# main.net
KiCad netlist of a schematic drawn in Altium Designer
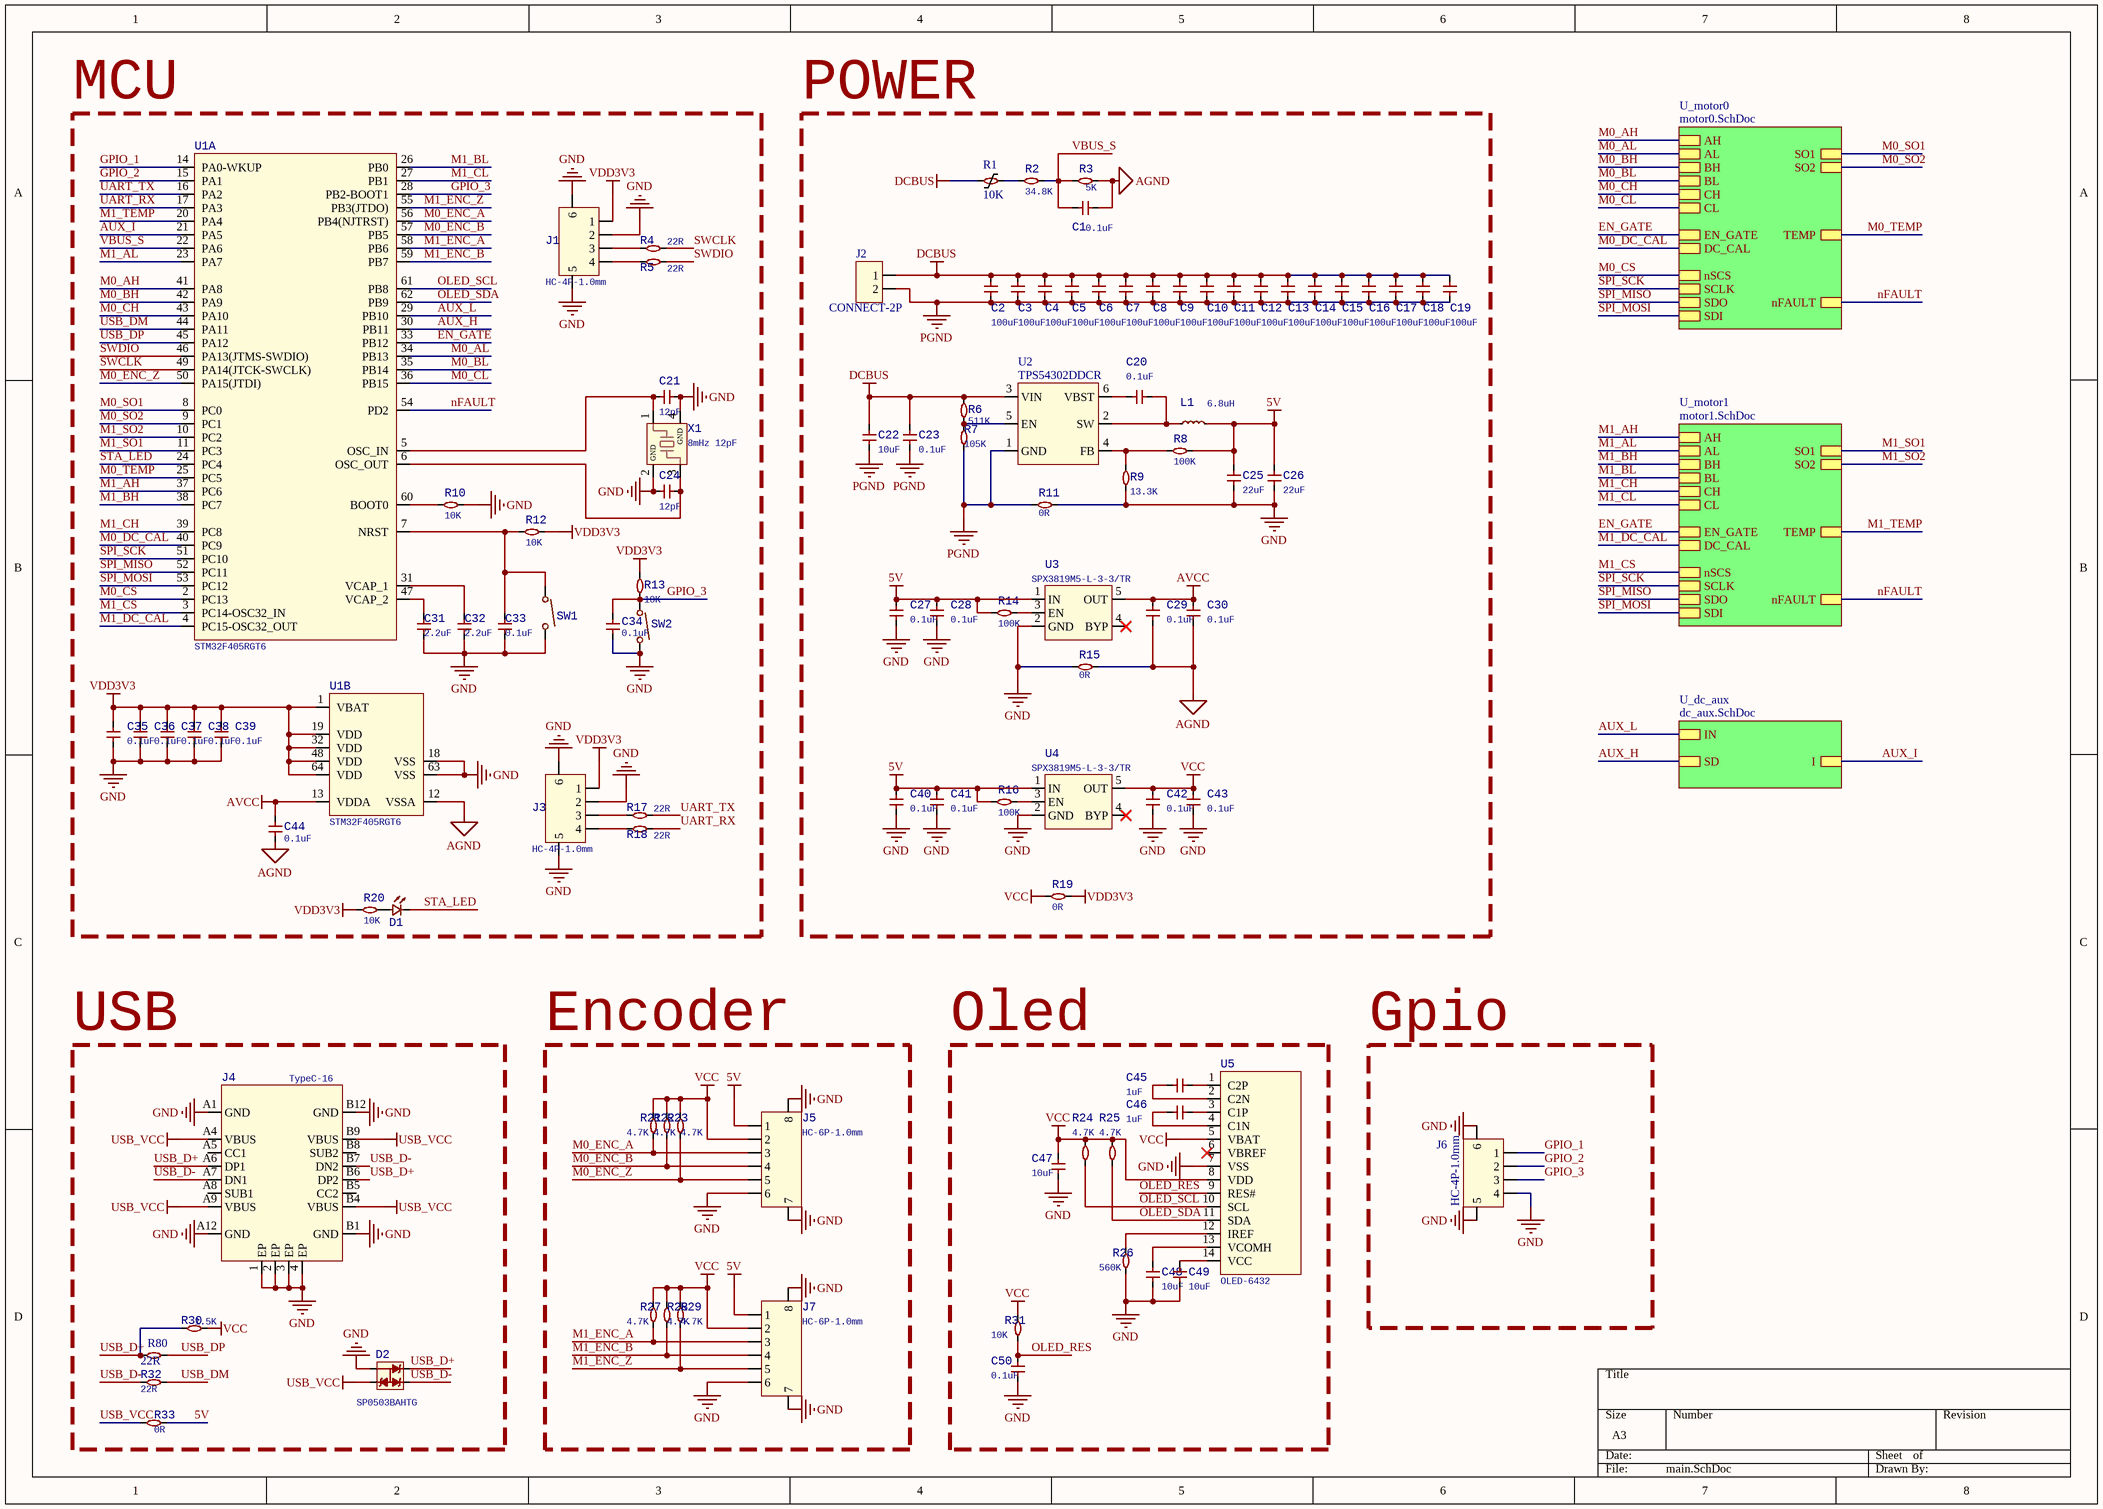
[diagram p0: main.SchDoc]

(export (version "E")
  (design (tool "Eeschema 10.0.6"))
  (components
    (comp (ref "C1")
      (value "0.1uF")
      (footprint "C0402")
      (description "贴片电容")
      (fields
        (field (name "MANUFACTURER") "SAMSUNG(三星)")
        (field (name "MANUFACTURER PART") "CL05A105KP5NNND")
      )
      (libsource (lib "schLibrary") (part "CAP"))
    )
    (comp (ref "C2")
      (value "100uF")
      (footprint "C1206")
      (description "贴片电容")
      (fields
        (field (name "MANUFACTURER") "SAMSUNG(三星)")
        (field (name "MANUFACTURER PART") "CL05A105KP5NNND")
      )
      (libsource (lib "schLibrary") (part "CAP"))
    )
    (comp (ref "C3")
      (value "100uF")
      (footprint "C1206")
      (description "贴片电容")
      (fields
        (field (name "MANUFACTURER") "SAMSUNG(三星)")
        (field (name "MANUFACTURER PART") "CL05A105KP5NNND")
      )
      (libsource (lib "schLibrary") (part "CAP"))
    )
    (comp (ref "C4")
      (value "100uF")
      (footprint "C1206")
      (description "贴片电容")
      (fields
        (field (name "MANUFACTURER") "SAMSUNG(三星)")
        (field (name "MANUFACTURER PART") "CL05A105KP5NNND")
      )
      (libsource (lib "schLibrary") (part "CAP"))
    )
    (comp (ref "C5")
      (value "100uF")
      (footprint "C1206")
      (description "贴片电容")
      (fields
        (field (name "MANUFACTURER") "SAMSUNG(三星)")
        (field (name "MANUFACTURER PART") "CL05A105KP5NNND")
      )
      (libsource (lib "schLibrary") (part "CAP"))
    )
    (comp (ref "C6")
      (value "100uF")
      (footprint "C1206")
      (description "贴片电容")
      (fields
        (field (name "MANUFACTURER") "SAMSUNG(三星)")
        (field (name "MANUFACTURER PART") "CL05A105KP5NNND")
      )
      (libsource (lib "schLibrary") (part "CAP"))
    )
    (comp (ref "C7")
      (value "100uF")
      (footprint "C1206")
      (description "贴片电容")
      (fields
        (field (name "MANUFACTURER") "SAMSUNG(三星)")
        (field (name "MANUFACTURER PART") "CL05A105KP5NNND")
      )
      (libsource (lib "schLibrary") (part "CAP"))
    )
    (comp (ref "C8")
      (value "100uF")
      (footprint "C1206")
      (description "贴片电容")
      (fields
        (field (name "MANUFACTURER") "SAMSUNG(三星)")
        (field (name "MANUFACTURER PART") "CL05A105KP5NNND")
      )
      (libsource (lib "schLibrary") (part "CAP"))
    )
    (comp (ref "C9")
      (value "100uF")
      (footprint "C1206")
      (description "贴片电容")
      (fields
        (field (name "MANUFACTURER") "SAMSUNG(三星)")
        (field (name "MANUFACTURER PART") "CL05A105KP5NNND")
      )
      (libsource (lib "schLibrary") (part "CAP"))
    )
    (comp (ref "C10")
      (value "100uF")
      (footprint "C1206")
      (description "贴片电容")
      (fields
        (field (name "MANUFACTURER") "SAMSUNG(三星)")
        (field (name "MANUFACTURER PART") "CL05A105KP5NNND")
      )
      (libsource (lib "schLibrary") (part "CAP"))
    )
    (comp (ref "C11")
      (value "100uF")
      (footprint "C1206")
      (description "贴片电容")
      (fields
        (field (name "MANUFACTURER") "SAMSUNG(三星)")
        (field (name "MANUFACTURER PART") "CL05A105KP5NNND")
      )
      (libsource (lib "schLibrary") (part "CAP"))
    )
    (comp (ref "C12")
      (value "100uF")
      (footprint "C1206")
      (description "贴片电容")
      (fields
        (field (name "MANUFACTURER") "SAMSUNG(三星)")
        (field (name "MANUFACTURER PART") "CL05A105KP5NNND")
      )
      (libsource (lib "schLibrary") (part "CAP"))
    )
    (comp (ref "C13")
      (value "100uF")
      (footprint "C1206")
      (description "贴片电容")
      (fields
        (field (name "MANUFACTURER") "SAMSUNG(三星)")
        (field (name "MANUFACTURER PART") "CL05A105KP5NNND")
      )
      (libsource (lib "schLibrary") (part "CAP"))
    )
    (comp (ref "C14")
      (value "100uF")
      (footprint "C1206")
      (description "贴片电容")
      (fields
        (field (name "MANUFACTURER") "SAMSUNG(三星)")
        (field (name "MANUFACTURER PART") "CL05A105KP5NNND")
      )
      (libsource (lib "schLibrary") (part "CAP"))
    )
    (comp (ref "C15")
      (value "100uF")
      (footprint "C1206")
      (description "贴片电容")
      (fields
        (field (name "MANUFACTURER") "SAMSUNG(三星)")
        (field (name "MANUFACTURER PART") "CL05A105KP5NNND")
      )
      (libsource (lib "schLibrary") (part "CAP"))
    )
    (comp (ref "C16")
      (value "100uF")
      (footprint "C1206")
      (description "贴片电容")
      (fields
        (field (name "MANUFACTURER") "SAMSUNG(三星)")
        (field (name "MANUFACTURER PART") "CL05A105KP5NNND")
      )
      (libsource (lib "schLibrary") (part "CAP"))
    )
    (comp (ref "C17")
      (value "100uF")
      (footprint "C1206")
      (description "贴片电容")
      (fields
        (field (name "MANUFACTURER") "SAMSUNG(三星)")
        (field (name "MANUFACTURER PART") "CL05A105KP5NNND")
      )
      (libsource (lib "schLibrary") (part "CAP"))
    )
    (comp (ref "C18")
      (value "100uF")
      (footprint "C1206")
      (description "贴片电容")
      (fields
        (field (name "MANUFACTURER") "SAMSUNG(三星)")
        (field (name "MANUFACTURER PART") "CL05A105KP5NNND")
      )
      (libsource (lib "schLibrary") (part "CAP"))
    )
    (comp (ref "C19")
      (value "100uF")
      (footprint "C1206")
      (description "贴片电容")
      (fields
        (field (name "MANUFACTURER") "SAMSUNG(三星)")
        (field (name "MANUFACTURER PART") "CL05A105KP5NNND")
      )
      (libsource (lib "schLibrary") (part "CAP"))
    )
    (comp (ref "C20")
      (value "0.1uF")
      (footprint "C0402")
      (description "贴片电容")
      (fields
        (field (name "MANUFACTURER") "SAMSUNG(三星)")
        (field (name "MANUFACTURER PART") "CL05A105KP5NNND")
      )
      (libsource (lib "schLibrary") (part "CAP"))
    )
    (comp (ref "C21")
      (value "12pF")
      (footprint "C0402")
      (description "贴片电容")
      (fields
        (field (name "MANUFACTURER") "SAMSUNG(三星)")
        (field (name "MANUFACTURER PART") "CL05A105KP5NNND")
      )
      (libsource (lib "schLibrary") (part "CAP"))
    )
    (comp (ref "C22")
      (value "10uF")
      (footprint "C0402")
      (description "贴片电容")
      (fields
        (field (name "MANUFACTURER") "SAMSUNG(三星)")
        (field (name "MANUFACTURER PART") "CL05A105KP5NNND")
      )
      (libsource (lib "schLibrary") (part "CAP"))
    )
    (comp (ref "C23")
      (value "0.1uF")
      (footprint "C0402")
      (description "贴片电容")
      (fields
        (field (name "MANUFACTURER") "SAMSUNG(三星)")
        (field (name "MANUFACTURER PART") "CL05A105KP5NNND")
      )
      (libsource (lib "schLibrary") (part "CAP"))
    )
    (comp (ref "C24")
      (value "12pF")
      (footprint "C0402")
      (description "贴片电容")
      (fields
        (field (name "MANUFACTURER") "SAMSUNG(三星)")
        (field (name "MANUFACTURER PART") "CL05A105KP5NNND")
      )
      (libsource (lib "schLibrary") (part "CAP"))
    )
    (comp (ref "C25")
      (value "22uF")
      (footprint "C0805")
      (description "贴片电容")
      (fields
        (field (name "MANUFACTURER") "SAMSUNG(三星)")
        (field (name "MANUFACTURER PART") "CL05A105KP5NNND")
      )
      (libsource (lib "schLibrary") (part "CAP"))
    )
    (comp (ref "C26")
      (value "22uF")
      (footprint "C0805")
      (description "贴片电容")
      (fields
        (field (name "MANUFACTURER") "SAMSUNG(三星)")
        (field (name "MANUFACTURER PART") "CL05A105KP5NNND")
      )
      (libsource (lib "schLibrary") (part "CAP"))
    )
    (comp (ref "C27")
      (value "0.1uF")
      (footprint "C0402")
      (description "贴片电容")
      (fields
        (field (name "MANUFACTURER") "SAMSUNG(三星)")
        (field (name "MANUFACTURER PART") "CL05A105KP5NNND")
      )
      (libsource (lib "schLibrary") (part "CAP"))
    )
    (comp (ref "C28")
      (value "0.1uF")
      (footprint "C0402")
      (description "贴片电容")
      (fields
        (field (name "MANUFACTURER") "SAMSUNG(三星)")
        (field (name "MANUFACTURER PART") "CL05A105KP5NNND")
      )
      (libsource (lib "schLibrary") (part "CAP"))
    )
    (comp (ref "C29")
      (value "0.1uF")
      (footprint "C0402")
      (description "贴片电容")
      (fields
        (field (name "MANUFACTURER") "SAMSUNG(三星)")
        (field (name "MANUFACTURER PART") "CL05A105KP5NNND")
      )
      (libsource (lib "schLibrary") (part "CAP"))
    )
    (comp (ref "C30")
      (value "0.1uF")
      (footprint "C0402")
      (description "贴片电容")
      (fields
        (field (name "MANUFACTURER") "SAMSUNG(三星)")
        (field (name "MANUFACTURER PART") "CL05A105KP5NNND")
      )
      (libsource (lib "schLibrary") (part "CAP"))
    )
    (comp (ref "C31")
      (value "2.2uF")
      (footprint "C0402")
      (description "贴片电容")
      (fields
        (field (name "MANUFACTURER") "SAMSUNG(三星)")
        (field (name "MANUFACTURER PART") "CL05A105KP5NNND")
      )
      (libsource (lib "schLibrary") (part "CAP"))
    )
    (comp (ref "C32")
      (value "2.2uF")
      (footprint "C0402")
      (description "贴片电容")
      (fields
        (field (name "MANUFACTURER") "SAMSUNG(三星)")
        (field (name "MANUFACTURER PART") "CL05A105KP5NNND")
      )
      (libsource (lib "schLibrary") (part "CAP"))
    )
    (comp (ref "C33")
      (value "0.1uF")
      (footprint "C0402")
      (description "贴片电容")
      (fields
        (field (name "MANUFACTURER") "SAMSUNG(三星)")
        (field (name "MANUFACTURER PART") "CL05A105KP5NNND")
      )
      (libsource (lib "schLibrary") (part "CAP"))
    )
    (comp (ref "C34")
      (value "0.1uF")
      (footprint "C0402")
      (description "贴片电容")
      (fields
        (field (name "MANUFACTURER") "SAMSUNG(三星)")
        (field (name "MANUFACTURER PART") "CL05A105KP5NNND")
      )
      (libsource (lib "schLibrary") (part "CAP"))
    )
    (comp (ref "C35")
      (value "0.1uF")
      (footprint "C0402")
      (description "贴片电容")
      (fields
        (field (name "MANUFACTURER") "SAMSUNG(三星)")
        (field (name "MANUFACTURER PART") "CL05A105KP5NNND")
      )
      (libsource (lib "schLibrary") (part "CAP"))
    )
    (comp (ref "C36")
      (value "0.1uF")
      (footprint "C0402")
      (description "贴片电容")
      (fields
        (field (name "MANUFACTURER") "SAMSUNG(三星)")
        (field (name "MANUFACTURER PART") "CL05A105KP5NNND")
      )
      (libsource (lib "schLibrary") (part "CAP"))
    )
    (comp (ref "C37")
      (value "0.1uF")
      (footprint "C0402")
      (description "贴片电容")
      (fields
        (field (name "MANUFACTURER") "SAMSUNG(三星)")
        (field (name "MANUFACTURER PART") "CL05A105KP5NNND")
      )
      (libsource (lib "schLibrary") (part "CAP"))
    )
    (comp (ref "C38")
      (value "0.1uF")
      (footprint "C0402")
      (description "贴片电容")
      (fields
        (field (name "MANUFACTURER") "SAMSUNG(三星)")
        (field (name "MANUFACTURER PART") "CL05A105KP5NNND")
      )
      (libsource (lib "schLibrary") (part "CAP"))
    )
    (comp (ref "C39")
      (value "0.1uF")
      (footprint "C0402")
      (description "贴片电容")
      (fields
        (field (name "MANUFACTURER") "SAMSUNG(三星)")
        (field (name "MANUFACTURER PART") "CL05A105KP5NNND")
      )
      (libsource (lib "schLibrary") (part "CAP"))
    )
    (comp (ref "C40")
      (value "0.1uF")
      (footprint "C0402")
      (description "贴片电容")
      (fields
        (field (name "MANUFACTURER") "SAMSUNG(三星)")
        (field (name "MANUFACTURER PART") "CL05A105KP5NNND")
      )
      (libsource (lib "schLibrary") (part "CAP"))
    )
    (comp (ref "C41")
      (value "0.1uF")
      (footprint "C0402")
      (description "贴片电容")
      (fields
        (field (name "MANUFACTURER") "SAMSUNG(三星)")
        (field (name "MANUFACTURER PART") "CL05A105KP5NNND")
      )
      (libsource (lib "schLibrary") (part "CAP"))
    )
    (comp (ref "C42")
      (value "0.1uF")
      (footprint "C0402")
      (description "贴片电容")
      (fields
        (field (name "MANUFACTURER") "SAMSUNG(三星)")
        (field (name "MANUFACTURER PART") "CL05A105KP5NNND")
      )
      (libsource (lib "schLibrary") (part "CAP"))
    )
    (comp (ref "C43")
      (value "0.1uF")
      (footprint "C0402")
      (description "贴片电容")
      (fields
        (field (name "MANUFACTURER") "SAMSUNG(三星)")
        (field (name "MANUFACTURER PART") "CL05A105KP5NNND")
      )
      (libsource (lib "schLibrary") (part "CAP"))
    )
    (comp (ref "C44")
      (value "0.1uF")
      (footprint "C0402")
      (description "贴片电容")
      (fields
        (field (name "MANUFACTURER") "SAMSUNG(三星)")
        (field (name "MANUFACTURER PART") "CL05A105KP5NNND")
      )
      (libsource (lib "schLibrary") (part "CAP"))
    )
    (comp (ref "C45")
      (value "1uF")
      (footprint "C0402")
      (description "贴片电容")
      (fields
        (field (name "MANUFACTURER") "SAMSUNG(三星)")
        (field (name "MANUFACTURER PART") "CL05A105KP5NNND")
      )
      (libsource (lib "schLibrary") (part "CAP"))
    )
    (comp (ref "C46")
      (value "1uF")
      (footprint "C0402")
      (description "贴片电容")
      (fields
        (field (name "MANUFACTURER") "SAMSUNG(三星)")
        (field (name "MANUFACTURER PART") "CL05A105KP5NNND")
      )
      (libsource (lib "schLibrary") (part "CAP"))
    )
    (comp (ref "C47")
      (value "10uF")
      (footprint "C0402")
      (description "贴片电容")
      (fields
        (field (name "MANUFACTURER") "SAMSUNG(三星)")
        (field (name "MANUFACTURER PART") "CL05A105KP5NNND")
      )
      (libsource (lib "schLibrary") (part "CAP"))
    )
    (comp (ref "C48")
      (value "10uF")
      (footprint "C0402")
      (description "贴片电容")
      (fields
        (field (name "MANUFACTURER") "SAMSUNG(三星)")
        (field (name "MANUFACTURER PART") "CL05A105KP5NNND")
      )
      (libsource (lib "schLibrary") (part "CAP"))
    )
    (comp (ref "C49")
      (value "10uF")
      (footprint "C0402")
      (description "贴片电容")
      (fields
        (field (name "MANUFACTURER") "SAMSUNG(三星)")
        (field (name "MANUFACTURER PART") "CL05A105KP5NNND")
      )
      (libsource (lib "schLibrary") (part "CAP"))
    )
    (comp (ref "C50")
      (value "0.1uF")
      (footprint "C0402")
      (description "贴片电容")
      (fields
        (field (name "MANUFACTURER") "SAMSUNG(三星)")
        (field (name "MANUFACTURER PART") "CL05A105KP5NNND")
      )
      (libsource (lib "schLibrary") (part "CAP"))
    )
    (comp (ref "D1")
      (value "LED")
      (footprint "LED-0402")
      (description "贴片发光二极管")
      (fields
        (field (name "MANUFACTURER") "SAMSUNG(三星)")
        (field (name "MANUFACTURER PART") "CL05A105KP5NNND")
      )
      (libsource (lib "schLibrary") (part "LED"))
    )
    (comp (ref "D2")
      (value "SP0503BAHTG")
      (footprint "SOT-143")
      (description "USB-三组 瞬态移植二极管")
      (libsource (lib "schLibrary") (part "SP0503BAHTG"))
    )
    (comp (ref "J1")
      (value "HC-4P-1.0mm")
      (footprint "SMD_4P_HC-1.0")
      (description "线对板连接器")
      (libsource (lib "schLibrary") (part "HC-4P-1.0mm"))
    )
    (comp (ref "J2")
      (value "CONNECT-2P")
      (footprint "CONNECT--EP-2P")
      (description "连接器")
      (libsource (lib "schLibrary") (part "CONNECT-2P"))
    )
    (comp (ref "J3")
      (value "HC-4P-1.0mm")
      (footprint "SMD_4P_HC-1.0")
      (description "线对板连接器")
      (libsource (lib "schLibrary") (part "HC-4P-1.0mm"))
    )
    (comp (ref "J4")
      (value "TypeC-16")
      (footprint "USB-SMD_TYPE-C-16P")
      (description "Type-C母座; 触点数量:16")
      (fields
        (field (name "MANUFACTURER") "kinghelm(金航标)")
        (field (name "MANUFACTURER PART") "KH-TYPE-C-16P")
      )
      (libsource (lib "schLibrary") (part "TypeC-16P"))
    )
    (comp (ref "J5")
      (value "HC-6P-1.0mm")
      (footprint "SMD_6P_HC-1.0")
      (description "线对板连接器")
      (libsource (lib "schLibrary") (part "HC-6P-1.0mm"))
    )
    (comp (ref "J6")
      (value "HC-4P-1.0mm")
      (footprint "SMD_4P_HC-1.0")
      (description "线对板连接器")
      (libsource (lib "schLibrary") (part "HC-4P-1.0mm"))
    )
    (comp (ref "J7")
      (value "HC-6P-1.0mm")
      (footprint "SMD_6P_HC-1.0")
      (description "线对板连接器")
      (libsource (lib "schLibrary") (part "HC-6P-1.0mm"))
    )
    (comp (ref "L1")
      (value "6.8uH")
      (footprint "L1008")
      (description "贴片电感")
      (libsource (lib "schLibrary") (part "IND"))
    )
    (comp (ref "R1")
      (value "10K")
      (footprint "R0402")
      (description "热敏电阻")
      (fields
        (field (name "MANUFACTURER") "UNI-ROYAL(厚声)")
        (field (name "MANUFACTURER PART") "0402WGF1001TCE")
      )
      (libsource (lib "schLibrary") (part "NTC"))
    )
    (comp (ref "R2")
      (value "34.8K")
      (footprint "R0402")
      (description "贴片电阻")
      (fields
        (field (name "MANUFACTURER") "UNI-ROYAL(厚声)")
        (field (name "MANUFACTURER PART") "0402WGF1001TCE")
      )
      (libsource (lib "schLibrary") (part "RES"))
    )
    (comp (ref "R3")
      (value "5K")
      (footprint "R0402")
      (description "贴片电阻")
      (fields
        (field (name "MANUFACTURER") "UNI-ROYAL(厚声)")
        (field (name "MANUFACTURER PART") "0402WGF1001TCE")
      )
      (libsource (lib "schLibrary") (part "RES"))
    )
    (comp (ref "R4")
      (value "22R")
      (footprint "R0402")
      (description "贴片电阻")
      (fields
        (field (name "MANUFACTURER") "UNI-ROYAL(厚声)")
        (field (name "MANUFACTURER PART") "0402WGF1001TCE")
      )
      (libsource (lib "schLibrary") (part "RES"))
    )
    (comp (ref "R5")
      (value "22R")
      (footprint "R0402")
      (description "贴片电阻")
      (fields
        (field (name "MANUFACTURER") "UNI-ROYAL(厚声)")
        (field (name "MANUFACTURER PART") "0402WGF1001TCE")
      )
      (libsource (lib "schLibrary") (part "RES"))
    )
    (comp (ref "R6")
      (value "511K")
      (footprint "R0402")
      (description "贴片电阻")
      (fields
        (field (name "MANUFACTURER") "UNI-ROYAL(厚声)")
        (field (name "MANUFACTURER PART") "0402WGF1001TCE")
      )
      (libsource (lib "schLibrary") (part "RES"))
    )
    (comp (ref "R7")
      (value "105K")
      (footprint "R0402")
      (description "贴片电阻")
      (fields
        (field (name "MANUFACTURER") "UNI-ROYAL(厚声)")
        (field (name "MANUFACTURER PART") "0402WGF1001TCE")
      )
      (libsource (lib "schLibrary") (part "RES"))
    )
    (comp (ref "R8")
      (value "100K")
      (footprint "R0402")
      (description "贴片电阻")
      (fields
        (field (name "MANUFACTURER") "UNI-ROYAL(厚声)")
        (field (name "MANUFACTURER PART") "0402WGF1001TCE")
      )
      (libsource (lib "schLibrary") (part "RES"))
    )
    (comp (ref "R9")
      (value "13.3K")
      (footprint "R0402")
      (description "贴片电阻")
      (fields
        (field (name "MANUFACTURER") "UNI-ROYAL(厚声)")
        (field (name "MANUFACTURER PART") "0402WGF1001TCE")
      )
      (libsource (lib "schLibrary") (part "RES"))
    )
    (comp (ref "R10")
      (value "10K")
      (footprint "R0402")
      (description "贴片电阻")
      (fields
        (field (name "MANUFACTURER") "UNI-ROYAL(厚声)")
        (field (name "MANUFACTURER PART") "0402WGF1001TCE")
      )
      (libsource (lib "schLibrary") (part "RES"))
    )
    (comp (ref "R11")
      (value "0R")
      (footprint "R0402")
      (description "贴片电阻")
      (fields
        (field (name "MANUFACTURER") "UNI-ROYAL(厚声)")
        (field (name "MANUFACTURER PART") "0402WGF1001TCE")
      )
      (libsource (lib "schLibrary") (part "RES"))
    )
    (comp (ref "R12")
      (value "10K")
      (footprint "R0402")
      (description "贴片电阻")
      (fields
        (field (name "MANUFACTURER") "UNI-ROYAL(厚声)")
        (field (name "MANUFACTURER PART") "0402WGF1001TCE")
      )
      (libsource (lib "schLibrary") (part "RES"))
    )
    (comp (ref "R13")
      (value "10K")
      (footprint "R0402")
      (description "贴片电阻")
      (fields
        (field (name "MANUFACTURER") "UNI-ROYAL(厚声)")
        (field (name "MANUFACTURER PART") "0402WGF1001TCE")
      )
      (libsource (lib "schLibrary") (part "RES"))
    )
    (comp (ref "R14")
      (value "100K")
      (footprint "R0402")
      (description "贴片电阻")
      (fields
        (field (name "MANUFACTURER") "UNI-ROYAL(厚声)")
        (field (name "MANUFACTURER PART") "0402WGF1001TCE")
      )
      (libsource (lib "schLibrary") (part "RES"))
    )
    (comp (ref "R15")
      (value "0R")
      (footprint "R0402")
      (description "贴片电阻")
      (fields
        (field (name "MANUFACTURER") "UNI-ROYAL(厚声)")
        (field (name "MANUFACTURER PART") "0402WGF1001TCE")
      )
      (libsource (lib "schLibrary") (part "RES"))
    )
    (comp (ref "R16")
      (value "100K")
      (footprint "R0402")
      (description "贴片电阻")
      (fields
        (field (name "MANUFACTURER") "UNI-ROYAL(厚声)")
        (field (name "MANUFACTURER PART") "0402WGF1001TCE")
      )
      (libsource (lib "schLibrary") (part "RES"))
    )
    (comp (ref "R17")
      (value "22R")
      (footprint "R0402")
      (description "贴片电阻")
      (fields
        (field (name "MANUFACTURER") "UNI-ROYAL(厚声)")
        (field (name "MANUFACTURER PART") "0402WGF1001TCE")
      )
      (libsource (lib "schLibrary") (part "RES"))
    )
    (comp (ref "R18")
      (value "22R")
      (footprint "R0402")
      (description "贴片电阻")
      (fields
        (field (name "MANUFACTURER") "UNI-ROYAL(厚声)")
        (field (name "MANUFACTURER PART") "0402WGF1001TCE")
      )
      (libsource (lib "schLibrary") (part "RES"))
    )
    (comp (ref "R19")
      (value "0R")
      (footprint "R0402")
      (description "贴片电阻")
      (fields
        (field (name "MANUFACTURER") "UNI-ROYAL(厚声)")
        (field (name "MANUFACTURER PART") "0402WGF1001TCE")
      )
      (libsource (lib "schLibrary") (part "RES"))
    )
    (comp (ref "R20")
      (value "10K")
      (footprint "R0402")
      (description "贴片电阻")
      (fields
        (field (name "MANUFACTURER") "UNI-ROYAL(厚声)")
        (field (name "MANUFACTURER PART") "0402WGF1001TCE")
      )
      (libsource (lib "schLibrary") (part "RES"))
    )
    (comp (ref "R21")
      (value "4.7K")
      (footprint "R0402")
      (description "贴片电阻")
      (fields
        (field (name "MANUFACTURER") "UNI-ROYAL(厚声)")
        (field (name "MANUFACTURER PART") "0402WGF1001TCE")
      )
      (libsource (lib "schLibrary") (part "RES"))
    )
    (comp (ref "R22")
      (value "4.7K")
      (footprint "R0402")
      (description "贴片电阻")
      (fields
        (field (name "MANUFACTURER") "UNI-ROYAL(厚声)")
        (field (name "MANUFACTURER PART") "0402WGF1001TCE")
      )
      (libsource (lib "schLibrary") (part "RES"))
    )
    (comp (ref "R23")
      (value "4.7K")
      (footprint "R0402")
      (description "贴片电阻")
      (fields
        (field (name "MANUFACTURER") "UNI-ROYAL(厚声)")
        (field (name "MANUFACTURER PART") "0402WGF1001TCE")
      )
      (libsource (lib "schLibrary") (part "RES"))
    )
    (comp (ref "R24")
      (value "4.7K")
      (footprint "R0402")
      (description "贴片电阻")
      (fields
        (field (name "MANUFACTURER") "UNI-ROYAL(厚声)")
        (field (name "MANUFACTURER PART") "0402WGF1001TCE")
      )
      (libsource (lib "schLibrary") (part "RES"))
    )
    (comp (ref "R25")
      (value "4.7K")
      (footprint "R0402")
      (description "贴片电阻")
      (fields
        (field (name "MANUFACTURER") "UNI-ROYAL(厚声)")
        (field (name "MANUFACTURER PART") "0402WGF1001TCE")
      )
      (libsource (lib "schLibrary") (part "RES"))
    )
    (comp (ref "R26")
      (value "560K")
      (footprint "R0402")
      (description "贴片电阻")
      (fields
        (field (name "MANUFACTURER") "UNI-ROYAL(厚声)")
        (field (name "MANUFACTURER PART") "0402WGF1001TCE")
      )
      (libsource (lib "schLibrary") (part "RES"))
    )
    (comp (ref "R27")
      (value "4.7K")
      (footprint "R0402")
      (description "贴片电阻")
      (fields
        (field (name "MANUFACTURER") "UNI-ROYAL(厚声)")
        (field (name "MANUFACTURER PART") "0402WGF1001TCE")
      )
      (libsource (lib "schLibrary") (part "RES"))
    )
    (comp (ref "R28")
      (value "4.7K")
      (footprint "R0402")
      (description "贴片电阻")
      (fields
        (field (name "MANUFACTURER") "UNI-ROYAL(厚声)")
        (field (name "MANUFACTURER PART") "0402WGF1001TCE")
      )
      (libsource (lib "schLibrary") (part "RES"))
    )
    (comp (ref "R29")
      (value "4.7K")
      (footprint "R0402")
      (description "贴片电阻")
      (fields
        (field (name "MANUFACTURER") "UNI-ROYAL(厚声)")
        (field (name "MANUFACTURER PART") "0402WGF1001TCE")
      )
      (libsource (lib "schLibrary") (part "RES"))
    )
    (comp (ref "R30")
      (value "1.5K")
      (footprint "R0402")
      (description "贴片电阻")
      (fields
        (field (name "MANUFACTURER") "UNI-ROYAL(厚声)")
        (field (name "MANUFACTURER PART") "0402WGF1001TCE")
      )
      (libsource (lib "schLibrary") (part "RES"))
    )
    (comp (ref "R31")
      (value "10K")
      (footprint "R0402")
      (description "贴片电阻")
      (fields
        (field (name "MANUFACTURER") "UNI-ROYAL(厚声)")
        (field (name "MANUFACTURER PART") "0402WGF1001TCE")
      )
      (libsource (lib "schLibrary") (part "RES"))
    )
    (comp (ref "R32")
      (value "22R")
      (footprint "R0402")
      (description "贴片电阻")
      (fields
        (field (name "MANUFACTURER") "UNI-ROYAL(厚声)")
        (field (name "MANUFACTURER PART") "0402WGF1001TCE")
      )
      (libsource (lib "schLibrary") (part "RES"))
    )
    (comp (ref "R33")
      (value "0R")
      (footprint "R0402")
      (description "贴片电阻")
      (fields
        (field (name "MANUFACTURER") "UNI-ROYAL(厚声)")
        (field (name "MANUFACTURER PART") "0402WGF1001TCE")
      )
      (libsource (lib "schLibrary") (part "RES"))
    )
    (comp (ref "R80")
      (value "22R")
      (footprint "R0402")
      (description "贴片电阻")
      (fields
        (field (name "MANUFACTURER") "UNI-ROYAL(厚声)")
        (field (name "MANUFACTURER PART") "0402WGF1001TCE")
      )
      (libsource (lib "schLibrary") (part "RES"))
    )
    (comp (ref "SW1")
      (value "3*4两脚按键")
      (footprint "SW-SMD_L4.0-W2.9")
      (description "3*4两脚贴片不带柱")
      (fields
        (field (name "MANUFACTURER") "BRIGHT(博瑞泰)")
        (field (name "MANUFACTURER PART") "TSA343G00-250J2")
      )
      (libsource (lib "schLibrary") (part "Switch"))
    )
    (comp (ref "SW2")
      (value "3*4两脚按键")
      (footprint "SW-SMD_L4.0-W2.9")
      (description "3*4两脚贴片不带柱")
      (fields
        (field (name "MANUFACTURER") "BRIGHT(博瑞泰)")
        (field (name "MANUFACTURER PART") "TSA343G00-250J2")
      )
      (libsource (lib "schLibrary") (part "Switch"))
    )
    (comp (ref "U1")
      (value "STM32F405RGT6")
      (footprint "LQFP-64_L10.0-W10.0-P0.50")
      (description "ST,MCU,CPU内核：ARM Cortex-M4 CPU最大主频：168MHz 程序存储容量：512KB 程序存储器类型：FLASH RAM总容量：192KB")
      (libsource (lib "schLibrary") (part "STM32F405RGT6"))
    )
    (comp (ref "U2")
      (value "TPS54302DDCR")
      (footprint "SOT-23-6")
      (description "降压DCDC\r\n输入4.5~28V \r\n输出596mV~28V\r\n3A")
      (libsource (lib "schLibrary") (part "TPS54302DDCR"))
    )
    (comp (ref "U3")
      (value "SPX3819M5-L-3-3/TR")
      (footprint "SOT-23-5")
      (description "LDO输入电压:16V;输出电压:3.3V")
      (fields (field (name "MANUFACTURER") "MaxLinear"))
      (libsource (lib "schLibrary") (part "SPX3819M5-L-3-3/TR"))
    )
    (comp (ref "U4")
      (value "SPX3819M5-L-3-3/TR")
      (footprint "SOT-23-5")
      (description "LDO输入电压:16V;输出电压:3.3V")
      (fields (field (name "MANUFACTURER") "MaxLinear"))
      (libsource (lib "schLibrary") (part "SPX3819M5-L-3-3/TR"))
    )
    (comp (ref "U5")
      (value "OLED-6432")
      (footprint "OLED-0.96-128x64")
      (libsource (lib "schLibrary") (part "OLED"))
    )
    (comp (ref "X1")
      (value "8mHz 12pF")
      (footprint "SMD2016-4P")
      (description "无源晶振  频率公差：±10ppm")
      (libsource (lib "schLibrary") (part "XTAL"))
    )
  )
  (nets
    (net (code "1") (name "/AUX_H") (class "Default")
      (node (ref "U1") (pin "30") (pinfunction "PB11_30") (pintype "passive"))
    )
    (net (code "2") (name "/AUX_I") (class "Default")
      (node (ref "U1") (pin "21") (pinfunction "PA5_21") (pintype "passive"))
    )
    (net (code "3") (name "/AUX_L") (class "Default")
      (node (ref "U1") (pin "29") (pinfunction "PB10_29") (pintype "passive"))
    )
    (net (code "4") (name "/EN_GATE") (class "Default")
      (node (ref "U1") (pin "33") (pinfunction "PB12_33") (pintype "passive"))
    )
    (net (code "5") (name "/GPIO_1") (class "Default")
      (node (ref "J6") (pin "1") (pinfunction "1_1") (pintype "passive"))
      (node (ref "U1") (pin "14") (pinfunction "PA0-WKUP_14") (pintype "passive"))
    )
    (net (code "6") (name "/GPIO_2") (class "Default")
      (node (ref "J6") (pin "2") (pinfunction "2_2") (pintype "passive"))
      (node (ref "U1") (pin "15") (pinfunction "PA1_15") (pintype "passive"))
    )
    (net (code "7") (name "/GPIO_3") (class "Default")
      (node (ref "C34") (pin "2") (pinfunction "2_2") (pintype "passive"))
      (node (ref "J6") (pin "3") (pinfunction "3_3") (pintype "passive"))
      (node (ref "R13") (pin "1") (pinfunction "1_1") (pintype "passive"))
      (node (ref "SW2") (pin "1") (pinfunction "1_1") (pintype "passive"))
      (node (ref "U1") (pin "28") (pinfunction "PB2-BOOT1_28") (pintype "passive"))
    )
    (net (code "8") (name "/M0_AH") (class "Default")
      (node (ref "U1") (pin "41") (pinfunction "PA8_41") (pintype "passive"))
    )
    (net (code "9") (name "/M0_AL") (class "Default")
      (node (ref "U1") (pin "34") (pinfunction "PB13_34") (pintype "passive"))
    )
    (net (code "10") (name "/M0_BH") (class "Default")
      (node (ref "U1") (pin "42") (pinfunction "PA9_42") (pintype "passive"))
    )
    (net (code "11") (name "/M0_BL") (class "Default")
      (node (ref "U1") (pin "35") (pinfunction "PB14_35") (pintype "passive"))
    )
    (net (code "12") (name "/M0_CH") (class "Default")
      (node (ref "U1") (pin "43") (pinfunction "PA10_43") (pintype "passive"))
    )
    (net (code "13") (name "/M0_CL") (class "Default")
      (node (ref "U1") (pin "36") (pinfunction "PB15_36") (pintype "passive"))
    )
    (net (code "14") (name "/M0_CS") (class "Default")
      (node (ref "U1") (pin "2") (pinfunction "PC13_2") (pintype "passive"))
    )
    (net (code "15") (name "/M0_DC_CAL") (class "Default")
      (node (ref "U1") (pin "40") (pinfunction "PC9_40") (pintype "passive"))
    )
    (net (code "16") (name "/M0_ENC_A") (class "Default")
      (node (ref "J5") (pin "3") (pinfunction "3_3") (pintype "passive"))
      (node (ref "R21") (pin "1") (pinfunction "1_1") (pintype "passive"))
      (node (ref "U1") (pin "56") (pinfunction "PB4(NJTRST)_56") (pintype "passive"))
    )
    (net (code "17") (name "/M0_ENC_B") (class "Default")
      (node (ref "J5") (pin "4") (pinfunction "4_4") (pintype "passive"))
      (node (ref "R22") (pin "1") (pinfunction "1_1") (pintype "passive"))
      (node (ref "U1") (pin "57") (pinfunction "PB5_57") (pintype "passive"))
    )
    (net (code "18") (name "/M0_ENC_Z") (class "Default")
      (node (ref "J5") (pin "5") (pinfunction "5_5") (pintype "passive"))
      (node (ref "R23") (pin "1") (pinfunction "1_1") (pintype "passive"))
      (node (ref "U1") (pin "50") (pinfunction "PA15(JTDI)_50") (pintype "passive"))
    )
    (net (code "19") (name "/M0_SO1") (class "Default")
      (node (ref "U1") (pin "8") (pinfunction "PC0_8") (pintype "passive"))
    )
    (net (code "20") (name "/M0_SO2") (class "Default")
      (node (ref "U1") (pin "9") (pinfunction "PC1_9") (pintype "passive"))
    )
    (net (code "21") (name "/M0_TEMP") (class "Default")
      (node (ref "U1") (pin "25") (pinfunction "PC5_25") (pintype "passive"))
    )
    (net (code "22") (name "/M1_AH") (class "Default")
      (node (ref "U1") (pin "37") (pinfunction "PC6_37") (pintype "passive"))
    )
    (net (code "23") (name "/M1_AL") (class "Default")
      (node (ref "U1") (pin "23") (pinfunction "PA7_23") (pintype "passive"))
    )
    (net (code "24") (name "/M1_BH") (class "Default")
      (node (ref "U1") (pin "38") (pinfunction "PC7_38") (pintype "passive"))
    )
    (net (code "25") (name "/M1_BL") (class "Default")
      (node (ref "U1") (pin "26") (pinfunction "PB0_26") (pintype "passive"))
    )
    (net (code "26") (name "/M1_CH") (class "Default")
      (node (ref "U1") (pin "39") (pinfunction "PC8_39") (pintype "passive"))
    )
    (net (code "27") (name "/M1_CL") (class "Default")
      (node (ref "U1") (pin "27") (pinfunction "PB1_27") (pintype "passive"))
    )
    (net (code "28") (name "/M1_CS") (class "Default")
      (node (ref "U1") (pin "3") (pinfunction "PC14-OSC32_IN_3") (pintype "passive"))
    )
    (net (code "29") (name "/M1_DC_CAL") (class "Default")
      (node (ref "U1") (pin "4") (pinfunction "PC15-OSC32_OUT_4") (pintype "passive"))
    )
    (net (code "30") (name "/M1_ENC_A") (class "Default")
      (node (ref "J7") (pin "3") (pinfunction "3_3") (pintype "passive"))
      (node (ref "R27") (pin "1") (pinfunction "1_1") (pintype "passive"))
      (node (ref "U1") (pin "58") (pinfunction "PB6_58") (pintype "passive"))
    )
    (net (code "31") (name "/M1_ENC_B") (class "Default")
      (node (ref "J7") (pin "4") (pinfunction "4_4") (pintype "passive"))
      (node (ref "R28") (pin "1") (pinfunction "1_1") (pintype "passive"))
      (node (ref "U1") (pin "59") (pinfunction "PB7_59") (pintype "passive"))
    )
    (net (code "32") (name "/M1_ENC_Z") (class "Default")
      (node (ref "J7") (pin "5") (pinfunction "5_5") (pintype "passive"))
      (node (ref "R29") (pin "1") (pinfunction "1_1") (pintype "passive"))
      (node (ref "U1") (pin "55") (pinfunction "PB3(JTDO)_55") (pintype "passive"))
    )
    (net (code "33") (name "/M1_SO1") (class "Default")
      (node (ref "U1") (pin "11") (pinfunction "PC3_11") (pintype "passive"))
    )
    (net (code "34") (name "/M1_SO2") (class "Default")
      (node (ref "U1") (pin "10") (pinfunction "PC2_10") (pintype "passive"))
    )
    (net (code "35") (name "/M1_TEMP") (class "Default")
      (node (ref "U1") (pin "20") (pinfunction "PA4_20") (pintype "passive"))
    )
    (net (code "36") (name "/OLED_RES") (class "Default")
      (node (ref "C50") (pin "1") (pinfunction "1_1") (pintype "passive"))
      (node (ref "R31") (pin "1") (pinfunction "1_1") (pintype "passive"))
      (node (ref "U5") (pin "9") (pinfunction "RES#_9") (pintype "passive"))
    )
    (net (code "37") (name "/OLED_SCL") (class "Default")
      (node (ref "R24") (pin "1") (pinfunction "1_1") (pintype "passive"))
      (node (ref "U1") (pin "61") (pinfunction "PB8_61") (pintype "passive"))
      (node (ref "U5") (pin "10") (pinfunction "SCL_10") (pintype "passive"))
    )
    (net (code "38") (name "/OLED_SDA") (class "Default")
      (node (ref "R25") (pin "1") (pinfunction "1_1") (pintype "passive"))
      (node (ref "U1") (pin "62") (pinfunction "PB9_62") (pintype "passive"))
      (node (ref "U5") (pin "11") (pinfunction "SDA_11") (pintype "passive"))
    )
    (net (code "39") (name "/SPI_MISO") (class "Default")
      (node (ref "U1") (pin "52") (pinfunction "PC11_52") (pintype "passive"))
    )
    (net (code "40") (name "/SPI_MOSI") (class "Default")
      (node (ref "U1") (pin "53") (pinfunction "PC12_53") (pintype "passive"))
    )
    (net (code "41") (name "/SPI_SCK") (class "Default")
      (node (ref "U1") (pin "51") (pinfunction "PC10_51") (pintype "passive"))
    )
    (net (code "42") (name "/STA_LED") (class "Default")
      (node (ref "D1") (pin "1") (pinfunction "1_1") (pintype "passive"))
      (node (ref "U1") (pin "24") (pinfunction "PC4_24") (pintype "passive"))
    )
    (net (code "43") (name "/SWCLK") (class "Default")
      (node (ref "R4") (pin "2") (pinfunction "2_2") (pintype "passive"))
      (node (ref "U1") (pin "49") (pinfunction "PA14(JTCK-SWCLK)_49") (pintype "passive"))
    )
    (net (code "44") (name "/SWDIO") (class "Default")
      (node (ref "R5") (pin "2") (pinfunction "2_2") (pintype "passive"))
      (node (ref "U1") (pin "46") (pinfunction "PA13(JTMS-SWDIO)_46") (pintype "passive"))
    )
    (net (code "45") (name "/UART_RX") (class "Default")
      (node (ref "R18") (pin "2") (pinfunction "2_2") (pintype "passive"))
      (node (ref "U1") (pin "17") (pinfunction "PA3_17") (pintype "passive"))
    )
    (net (code "46") (name "/UART_TX") (class "Default")
      (node (ref "R17") (pin "2") (pinfunction "2_2") (pintype "passive"))
      (node (ref "U1") (pin "16") (pinfunction "PA2_16") (pintype "passive"))
    )
    (net (code "47") (name "/USB_D+") (class "Default")
      (node (ref "D2") (pin "4") (pinfunction "4_4") (pintype "passive"))
      (node (ref "J4") (pin "A6") (pinfunction "DP1_A6") (pintype "passive"))
      (node (ref "J4") (pin "B6") (pinfunction "DP2_B6") (pintype "passive"))
      (node (ref "R30") (pin "1") (pinfunction "1_1") (pintype "passive"))
      (node (ref "R80") (pin "1") (pinfunction "1_1") (pintype "passive"))
    )
    (net (code "48") (name "/USB_D-") (class "Default")
      (node (ref "D2") (pin "3") (pinfunction "3_3") (pintype "passive"))
      (node (ref "J4") (pin "A7") (pinfunction "DN1_A7") (pintype "passive"))
      (node (ref "J4") (pin "B7") (pinfunction "DN2_B7") (pintype "passive"))
      (node (ref "R32") (pin "1") (pinfunction "1_1") (pintype "passive"))
    )
    (net (code "49") (name "/USB_DM") (class "Default")
      (node (ref "R32") (pin "2") (pinfunction "2_2") (pintype "passive"))
      (node (ref "U1") (pin "44") (pinfunction "PA11_44") (pintype "passive"))
    )
    (net (code "50") (name "/USB_DP") (class "Default")
      (node (ref "R80") (pin "2") (pinfunction "2_2") (pintype "passive"))
      (node (ref "U1") (pin "45") (pinfunction "PA12_45") (pintype "passive"))
    )
    (net (code "51") (name "/VBUS_S") (class "Default")
      (node (ref "C1") (pin "1") (pinfunction "1_1") (pintype "passive"))
      (node (ref "R2") (pin "1") (pinfunction "1_1") (pintype "passive"))
      (node (ref "R3") (pin "2") (pinfunction "2_2") (pintype "passive"))
      (node (ref "U1") (pin "22") (pinfunction "PA6_22") (pintype "passive"))
    )
    (net (code "52") (name "/nFAULT") (class "Default")
      (node (ref "U1") (pin "54") (pinfunction "PD2_54") (pintype "passive"))
    )
    (net (code "53") (name "5V") (class "Default")
      (node (ref "C25") (pin "1") (pinfunction "1_1") (pintype "passive"))
      (node (ref "C26") (pin "1") (pinfunction "1_1") (pintype "passive"))
      (node (ref "C27") (pin "1") (pinfunction "1_1") (pintype "passive"))
      (node (ref "C28") (pin "1") (pinfunction "1_1") (pintype "passive"))
      (node (ref "C40") (pin "1") (pinfunction "1_1") (pintype "passive"))
      (node (ref "C41") (pin "1") (pinfunction "1_1") (pintype "passive"))
      (node (ref "J5") (pin "1") (pinfunction "1_1") (pintype "passive"))
      (node (ref "J7") (pin "1") (pinfunction "1_1") (pintype "passive"))
      (node (ref "L1") (pin "2") (pinfunction "2_2") (pintype "passive"))
      (node (ref "R14") (pin "2") (pinfunction "2_2") (pintype "passive"))
      (node (ref "R16") (pin "2") (pinfunction "2_2") (pintype "passive"))
      (node (ref "R33") (pin "2") (pinfunction "2_2") (pintype "passive"))
      (node (ref "R8") (pin "2") (pinfunction "2_2") (pintype "passive"))
      (node (ref "U3") (pin "1") (pinfunction "IN_1") (pintype "passive"))
      (node (ref "U4") (pin "1") (pinfunction "IN_1") (pintype "passive"))
    )
    (net (code "54") (name "AGND") (class "Default")
      (node (ref "C1") (pin "2") (pinfunction "2_2") (pintype "passive"))
      (node (ref "C29") (pin "2") (pinfunction "2_2") (pintype "passive"))
      (node (ref "C30") (pin "2") (pinfunction "2_2") (pintype "passive"))
      (node (ref "C44") (pin "2") (pinfunction "2_2") (pintype "passive"))
      (node (ref "R15") (pin "1") (pinfunction "1_1") (pintype "passive"))
      (node (ref "R3") (pin "1") (pinfunction "1_1") (pintype "passive"))
      (node (ref "U1") (pin "12") (pinfunction "VSSA_12") (pintype "passive"))
    )
    (net (code "55") (name "AVCC") (class "Default")
      (node (ref "C29") (pin "1") (pinfunction "1_1") (pintype "passive"))
      (node (ref "C30") (pin "1") (pinfunction "1_1") (pintype "passive"))
      (node (ref "C44") (pin "1") (pinfunction "1_1") (pintype "passive"))
      (node (ref "U1") (pin "13") (pinfunction "VDDA_13") (pintype "passive"))
      (node (ref "U3") (pin "5") (pinfunction "OUT_5") (pintype "passive"))
    )
    (net (code "56") (name "DCBUS") (class "Default")
      (node (ref "C10") (pin "1") (pinfunction "1_1") (pintype "passive"))
      (node (ref "C11") (pin "1") (pinfunction "1_1") (pintype "passive"))
      (node (ref "C12") (pin "1") (pinfunction "1_1") (pintype "passive"))
      (node (ref "C13") (pin "1") (pinfunction "1_1") (pintype "passive"))
      (node (ref "C14") (pin "1") (pinfunction "1_1") (pintype "passive"))
      (node (ref "C15") (pin "1") (pinfunction "1_1") (pintype "passive"))
      (node (ref "C16") (pin "1") (pinfunction "1_1") (pintype "passive"))
      (node (ref "C17") (pin "1") (pinfunction "1_1") (pintype "passive"))
      (node (ref "C18") (pin "1") (pinfunction "1_1") (pintype "passive"))
      (node (ref "C19") (pin "1") (pinfunction "1_1") (pintype "passive"))
      (node (ref "C2") (pin "1") (pinfunction "1_1") (pintype "passive"))
      (node (ref "C22") (pin "1") (pinfunction "1_1") (pintype "passive"))
      (node (ref "C23") (pin "1") (pinfunction "1_1") (pintype "passive"))
      (node (ref "C3") (pin "1") (pinfunction "1_1") (pintype "passive"))
      (node (ref "C4") (pin "1") (pinfunction "1_1") (pintype "passive"))
      (node (ref "C5") (pin "1") (pinfunction "1_1") (pintype "passive"))
      (node (ref "C6") (pin "1") (pinfunction "1_1") (pintype "passive"))
      (node (ref "C7") (pin "1") (pinfunction "1_1") (pintype "passive"))
      (node (ref "C8") (pin "1") (pinfunction "1_1") (pintype "passive"))
      (node (ref "C9") (pin "1") (pinfunction "1_1") (pintype "passive"))
      (node (ref "J2") (pin "1") (pinfunction "1_1") (pintype "passive"))
      (node (ref "R1") (pin "2") (pinfunction "2_2") (pintype "passive"))
      (node (ref "R6") (pin "2") (pinfunction "2_2") (pintype "passive"))
      (node (ref "U2") (pin "3") (pinfunction "VIN_3") (pintype "passive"))
    )
    (net (code "57") (name "GND") (class "Default")
      (node (ref "C21") (pin "2") (pinfunction "2_2") (pintype "passive"))
      (node (ref "C24") (pin "2") (pinfunction "2_2") (pintype "passive"))
      (node (ref "C25") (pin "2") (pinfunction "2_2") (pintype "passive"))
      (node (ref "C26") (pin "2") (pinfunction "2_2") (pintype "passive"))
      (node (ref "C27") (pin "2") (pinfunction "2_2") (pintype "passive"))
      (node (ref "C28") (pin "2") (pinfunction "2_2") (pintype "passive"))
      (node (ref "C31") (pin "2") (pinfunction "2_2") (pintype "passive"))
      (node (ref "C32") (pin "2") (pinfunction "2_2") (pintype "passive"))
      (node (ref "C33") (pin "1") (pinfunction "1_1") (pintype "passive"))
      (node (ref "C34") (pin "1") (pinfunction "1_1") (pintype "passive"))
      (node (ref "C35") (pin "2") (pinfunction "2_2") (pintype "passive"))
      (node (ref "C36") (pin "2") (pinfunction "2_2") (pintype "passive"))
      (node (ref "C37") (pin "2") (pinfunction "2_2") (pintype "passive"))
      (node (ref "C38") (pin "2") (pinfunction "2_2") (pintype "passive"))
      (node (ref "C39") (pin "2") (pinfunction "2_2") (pintype "passive"))
      (node (ref "C40") (pin "2") (pinfunction "2_2") (pintype "passive"))
      (node (ref "C41") (pin "2") (pinfunction "2_2") (pintype "passive"))
      (node (ref "C42") (pin "2") (pinfunction "2_2") (pintype "passive"))
      (node (ref "C43") (pin "2") (pinfunction "2_2") (pintype "passive"))
      (node (ref "C47") (pin "2") (pinfunction "2_2") (pintype "passive"))
      (node (ref "C48") (pin "2") (pinfunction "2_2") (pintype "passive"))
      (node (ref "C49") (pin "2") (pinfunction "2_2") (pintype "passive"))
      (node (ref "C50") (pin "2") (pinfunction "2_2") (pintype "passive"))
      (node (ref "D2") (pin "1") (pinfunction "1_1") (pintype "passive"))
      (node (ref "J1") (pin "2") (pinfunction "2_2") (pintype "passive"))
      (node (ref "J1") (pin "5") (pinfunction "5_5") (pintype "passive"))
      (node (ref "J1") (pin "6") (pinfunction "6_6") (pintype "passive"))
      (node (ref "J3") (pin "2") (pinfunction "2_2") (pintype "passive"))
      (node (ref "J3") (pin "5") (pinfunction "5_5") (pintype "passive"))
      (node (ref "J3") (pin "6") (pinfunction "6_6") (pintype "passive"))
      (node (ref "J4") (pin "1") (pinfunction "EP_1") (pintype "passive"))
      (node (ref "J4") (pin "2") (pinfunction "EP_2") (pintype "passive"))
      (node (ref "J4") (pin "3") (pinfunction "EP_3") (pintype "passive"))
      (node (ref "J4") (pin "4") (pinfunction "EP_4") (pintype "passive"))
      (node (ref "J4") (pin "A1") (pinfunction "GND_A1") (pintype "passive"))
      (node (ref "J4") (pin "A12") (pinfunction "GND_A12") (pintype "passive"))
      (node (ref "J4") (pin "B1") (pinfunction "GND_B1") (pintype "passive"))
      (node (ref "J4") (pin "B12") (pinfunction "GND_B12") (pintype "passive"))
      (node (ref "J5") (pin "6") (pinfunction "6_6") (pintype "passive"))
      (node (ref "J5") (pin "7") (pinfunction "7_7") (pintype "passive"))
      (node (ref "J5") (pin "8") (pinfunction "8_8") (pintype "passive"))
      (node (ref "J6") (pin "4") (pinfunction "4_4") (pintype "passive"))
      (node (ref "J6") (pin "5") (pinfunction "5_5") (pintype "passive"))
      (node (ref "J6") (pin "6") (pinfunction "6_6") (pintype "passive"))
      (node (ref "J7") (pin "6") (pinfunction "6_6") (pintype "passive"))
      (node (ref "J7") (pin "7") (pinfunction "7_7") (pintype "passive"))
      (node (ref "J7") (pin "8") (pinfunction "8_8") (pintype "passive"))
      (node (ref "R10") (pin "2") (pinfunction "2_2") (pintype "passive"))
      (node (ref "R11") (pin "1") (pinfunction "1_1") (pintype "passive"))
      (node (ref "R15") (pin "2") (pinfunction "2_2") (pintype "passive"))
      (node (ref "R26") (pin "1") (pinfunction "1_1") (pintype "passive"))
      (node (ref "R9") (pin "1") (pinfunction "1_1") (pintype "passive"))
      (node (ref "SW1") (pin "2") (pinfunction "2_2") (pintype "passive"))
      (node (ref "SW2") (pin "2") (pinfunction "2_2") (pintype "passive"))
      (node (ref "U1") (pin "18") (pinfunction "VSS_18") (pintype "passive"))
      (node (ref "U1") (pin "63") (pinfunction "VSS_63") (pintype "passive"))
      (node (ref "U3") (pin "2") (pinfunction "GND_2") (pintype "passive"))
      (node (ref "U4") (pin "2") (pinfunction "GND_2") (pintype "passive"))
      (node (ref "U5") (pin "7") (pinfunction "VSS_7") (pintype "passive"))
      (node (ref "X1") (pin "2") (pinfunction "GND_2") (pintype "passive"))
      (node (ref "X1") (pin "4") (pinfunction "GND_4") (pintype "passive"))
    )
    (net (code "58") (name "Net-(D1-Pad2)") (class "Default")
      (node (ref "D1") (pin "2") (pinfunction "2_2") (pintype "passive"))
      (node (ref "R20") (pin "2") (pinfunction "2_2") (pintype "passive"))
    )
    (net (code "59") (name "Net-(J1-Pad3)") (class "Default")
      (node (ref "J1") (pin "3") (pinfunction "3_3") (pintype "passive"))
      (node (ref "R4") (pin "1") (pinfunction "1_1") (pintype "passive"))
    )
    (net (code "60") (name "Net-(J1-Pad4)") (class "Default")
      (node (ref "J1") (pin "4") (pinfunction "4_4") (pintype "passive"))
      (node (ref "R5") (pin "1") (pinfunction "1_1") (pintype "passive"))
    )
    (net (code "61") (name "Net-(J3-Pad3)") (class "Default")
      (node (ref "J3") (pin "3") (pinfunction "3_3") (pintype "passive"))
      (node (ref "R17") (pin "1") (pinfunction "1_1") (pintype "passive"))
    )
    (net (code "62") (name "Net-(J3-Pad4)") (class "Default")
      (node (ref "J3") (pin "4") (pinfunction "4_4") (pintype "passive"))
      (node (ref "R18") (pin "1") (pinfunction "1_1") (pintype "passive"))
    )
    (net (code "63") (name "Net-(R1-Pad1)") (class "Default")
      (node (ref "R1") (pin "1") (pinfunction "1_1") (pintype "passive"))
      (node (ref "R2") (pin "2") (pinfunction "2_2") (pintype "passive"))
    )
    (net (code "64") (name "Net-(U1A-BOOT0)") (class "Default")
      (node (ref "R10") (pin "1") (pinfunction "1_1") (pintype "passive"))
      (node (ref "U1") (pin "60") (pinfunction "BOOT0_60") (pintype "passive"))
    )
    (net (code "65") (name "Net-(U1A-NRST)") (class "Default")
      (node (ref "C33") (pin "2") (pinfunction "2_2") (pintype "passive"))
      (node (ref "R12") (pin "1") (pinfunction "1_1") (pintype "passive"))
      (node (ref "SW1") (pin "1") (pinfunction "1_1") (pintype "passive"))
      (node (ref "U1") (pin "7") (pinfunction "NRST_7") (pintype "passive"))
    )
    (net (code "66") (name "Net-(U1A-OSC_IN)") (class "Default")
      (node (ref "C21") (pin "1") (pinfunction "1_1") (pintype "passive"))
      (node (ref "U1") (pin "5") (pinfunction "OSC_IN_5") (pintype "passive"))
      (node (ref "X1") (pin "1") (pinfunction "1_1") (pintype "passive"))
    )
    (net (code "67") (name "Net-(U1A-OSC_OUT)") (class "Default")
      (node (ref "C24") (pin "1") (pinfunction "1_1") (pintype "passive"))
      (node (ref "U1") (pin "6") (pinfunction "OSC_OUT_6") (pintype "passive"))
      (node (ref "X1") (pin "3") (pinfunction "1_3") (pintype "passive"))
    )
    (net (code "68") (name "Net-(U1A-VCAP_1)") (class "Default")
      (node (ref "C32") (pin "1") (pinfunction "1_1") (pintype "passive"))
      (node (ref "U1") (pin "31") (pinfunction "VCAP_1_31") (pintype "passive"))
    )
    (net (code "69") (name "Net-(U1A-VCAP_2)") (class "Default")
      (node (ref "C31") (pin "1") (pinfunction "1_1") (pintype "passive"))
      (node (ref "U1") (pin "47") (pinfunction "VCAP_2_47") (pintype "passive"))
    )
    (net (code "70") (name "Net-(U2-EN)") (class "Default")
      (node (ref "R6") (pin "1") (pinfunction "1_1") (pintype "passive"))
      (node (ref "R7") (pin "1") (pinfunction "1_1") (pintype "passive"))
      (node (ref "U2") (pin "5") (pinfunction "EN_5") (pintype "passive"))
    )
    (net (code "71") (name "Net-(U2-FB)") (class "Default")
      (node (ref "R8") (pin "1") (pinfunction "1_1") (pintype "passive"))
      (node (ref "R9") (pin "2") (pinfunction "2_2") (pintype "passive"))
      (node (ref "U2") (pin "4") (pinfunction "FB_4") (pintype "passive"))
    )
    (net (code "72") (name "Net-(U2-SW)") (class "Default")
      (node (ref "C20") (pin "1") (pinfunction "1_1") (pintype "passive"))
      (node (ref "L1") (pin "1") (pinfunction "1_1") (pintype "passive"))
      (node (ref "U2") (pin "2") (pinfunction "SW_2") (pintype "passive"))
    )
    (net (code "73") (name "Net-(U2-VBST)") (class "Default")
      (node (ref "C20") (pin "2") (pinfunction "2_2") (pintype "passive"))
      (node (ref "U2") (pin "6") (pinfunction "VBST_6") (pintype "passive"))
    )
    (net (code "74") (name "Net-(U3-EN)") (class "Default")
      (node (ref "R14") (pin "1") (pinfunction "1_1") (pintype "passive"))
      (node (ref "U3") (pin "3") (pinfunction "EN_3") (pintype "passive"))
    )
    (net (code "75") (name "Net-(U4-EN)") (class "Default")
      (node (ref "R16") (pin "1") (pinfunction "1_1") (pintype "passive"))
      (node (ref "U4") (pin "3") (pinfunction "EN_3") (pintype "passive"))
    )
    (net (code "76") (name "Net-(U5-C1N)") (class "Default")
      (node (ref "C46") (pin "2") (pinfunction "2_2") (pintype "passive"))
      (node (ref "U5") (pin "4") (pinfunction "C1N_4") (pintype "passive"))
    )
    (net (code "77") (name "Net-(U5-C1P)") (class "Default")
      (node (ref "C46") (pin "1") (pinfunction "1_1") (pintype "passive"))
      (node (ref "U5") (pin "3") (pinfunction "C1P_3") (pintype "passive"))
    )
    (net (code "78") (name "Net-(U5-C2N)") (class "Default")
      (node (ref "C45") (pin "2") (pinfunction "2_2") (pintype "passive"))
      (node (ref "U5") (pin "2") (pinfunction "C2N_2") (pintype "passive"))
    )
    (net (code "79") (name "Net-(U5-C2P)") (class "Default")
      (node (ref "C45") (pin "1") (pinfunction "1_1") (pintype "passive"))
      (node (ref "U5") (pin "1") (pinfunction "C2P_1") (pintype "passive"))
    )
    (net (code "80") (name "Net-(U5-IREF)") (class "Default")
      (node (ref "R26") (pin "2") (pinfunction "2_2") (pintype "passive"))
      (node (ref "U5") (pin "12") (pinfunction "IREF_12") (pintype "passive"))
    )
    (net (code "81") (name "Net-(U5-VCC)") (class "Default")
      (node (ref "C49") (pin "1") (pinfunction "1_1") (pintype "passive"))
      (node (ref "U5") (pin "14") (pinfunction "VCC_14") (pintype "passive"))
    )
    (net (code "82") (name "Net-(U5-VCOMH)") (class "Default")
      (node (ref "C48") (pin "1") (pinfunction "1_1") (pintype "passive"))
      (node (ref "U5") (pin "13") (pinfunction "VCOMH_13") (pintype "passive"))
    )
    (net (code "83") (name "PGND") (class "Default")
      (node (ref "C10") (pin "2") (pinfunction "2_2") (pintype "passive"))
      (node (ref "C11") (pin "2") (pinfunction "2_2") (pintype "passive"))
      (node (ref "C12") (pin "2") (pinfunction "2_2") (pintype "passive"))
      (node (ref "C13") (pin "2") (pinfunction "2_2") (pintype "passive"))
      (node (ref "C14") (pin "2") (pinfunction "2_2") (pintype "passive"))
      (node (ref "C15") (pin "2") (pinfunction "2_2") (pintype "passive"))
      (node (ref "C16") (pin "2") (pinfunction "2_2") (pintype "passive"))
      (node (ref "C17") (pin "2") (pinfunction "2_2") (pintype "passive"))
      (node (ref "C18") (pin "2") (pinfunction "2_2") (pintype "passive"))
      (node (ref "C19") (pin "2") (pinfunction "2_2") (pintype "passive"))
      (node (ref "C2") (pin "2") (pinfunction "2_2") (pintype "passive"))
      (node (ref "C22") (pin "2") (pinfunction "2_2") (pintype "passive"))
      (node (ref "C23") (pin "2") (pinfunction "2_2") (pintype "passive"))
      (node (ref "C3") (pin "2") (pinfunction "2_2") (pintype "passive"))
      (node (ref "C4") (pin "2") (pinfunction "2_2") (pintype "passive"))
      (node (ref "C5") (pin "2") (pinfunction "2_2") (pintype "passive"))
      (node (ref "C6") (pin "2") (pinfunction "2_2") (pintype "passive"))
      (node (ref "C7") (pin "2") (pinfunction "2_2") (pintype "passive"))
      (node (ref "C8") (pin "2") (pinfunction "2_2") (pintype "passive"))
      (node (ref "C9") (pin "2") (pinfunction "2_2") (pintype "passive"))
      (node (ref "J2") (pin "2") (pinfunction "2_2") (pintype "passive"))
      (node (ref "R11") (pin "2") (pinfunction "2_2") (pintype "passive"))
      (node (ref "R7") (pin "2") (pinfunction "2_2") (pintype "passive"))
      (node (ref "U2") (pin "1") (pinfunction "GND_1") (pintype "passive"))
    )
    (net (code "84") (name "USB_VCC") (class "Default")
      (node (ref "D2") (pin "2") (pinfunction "2_2") (pintype "passive"))
      (node (ref "J4") (pin "A4") (pinfunction "VBUS_A4") (pintype "passive"))
      (node (ref "J4") (pin "A9") (pinfunction "VBUS_A9") (pintype "passive"))
      (node (ref "J4") (pin "B4") (pinfunction "VBUS_B4") (pintype "passive"))
      (node (ref "J4") (pin "B9") (pinfunction "VBUS_B9") (pintype "passive"))
      (node (ref "R33") (pin "1") (pinfunction "1_1") (pintype "passive"))
    )
    (net (code "85") (name "VCC") (class "Default")
      (node (ref "C42") (pin "1") (pinfunction "1_1") (pintype "passive"))
      (node (ref "C43") (pin "1") (pinfunction "1_1") (pintype "passive"))
      (node (ref "C47") (pin "1") (pinfunction "1_1") (pintype "passive"))
      (node (ref "J5") (pin "2") (pinfunction "2_2") (pintype "passive"))
      (node (ref "J7") (pin "2") (pinfunction "2_2") (pintype "passive"))
      (node (ref "R19") (pin "1") (pinfunction "1_1") (pintype "passive"))
      (node (ref "R21") (pin "2") (pinfunction "2_2") (pintype "passive"))
      (node (ref "R22") (pin "2") (pinfunction "2_2") (pintype "passive"))
      (node (ref "R23") (pin "2") (pinfunction "2_2") (pintype "passive"))
      (node (ref "R24") (pin "2") (pinfunction "2_2") (pintype "passive"))
      (node (ref "R25") (pin "2") (pinfunction "2_2") (pintype "passive"))
      (node (ref "R27") (pin "2") (pinfunction "2_2") (pintype "passive"))
      (node (ref "R28") (pin "2") (pinfunction "2_2") (pintype "passive"))
      (node (ref "R29") (pin "2") (pinfunction "2_2") (pintype "passive"))
      (node (ref "R30") (pin "2") (pinfunction "2_2") (pintype "passive"))
      (node (ref "R31") (pin "2") (pinfunction "2_2") (pintype "passive"))
      (node (ref "U4") (pin "5") (pinfunction "OUT_5") (pintype "passive"))
      (node (ref "U5") (pin "5") (pinfunction "VBAT_5") (pintype "passive"))
      (node (ref "U5") (pin "8") (pinfunction "VDD_8") (pintype "passive"))
    )
    (net (code "86") (name "VDD3V3") (class "Default")
      (node (ref "C35") (pin "1") (pinfunction "1_1") (pintype "passive"))
      (node (ref "C36") (pin "1") (pinfunction "1_1") (pintype "passive"))
      (node (ref "C37") (pin "1") (pinfunction "1_1") (pintype "passive"))
      (node (ref "C38") (pin "1") (pinfunction "1_1") (pintype "passive"))
      (node (ref "C39") (pin "1") (pinfunction "1_1") (pintype "passive"))
      (node (ref "J1") (pin "1") (pinfunction "1_1") (pintype "passive"))
      (node (ref "J3") (pin "1") (pinfunction "1_1") (pintype "passive"))
      (node (ref "R12") (pin "2") (pinfunction "2_2") (pintype "passive"))
      (node (ref "R13") (pin "2") (pinfunction "2_2") (pintype "passive"))
      (node (ref "R19") (pin "2") (pinfunction "2_2") (pintype "passive"))
      (node (ref "R20") (pin "1") (pinfunction "1_1") (pintype "passive"))
      (node (ref "U1") (pin "1") (pinfunction "VBAT_1") (pintype "passive"))
      (node (ref "U1") (pin "19") (pinfunction "VDD_19") (pintype "passive"))
      (node (ref "U1") (pin "32") (pinfunction "VDD_32") (pintype "passive"))
      (node (ref "U1") (pin "48") (pinfunction "VDD_48") (pintype "passive"))
      (node (ref "U1") (pin "64") (pinfunction "VDD_64") (pintype "passive"))
    )
    (net (code "87") (name "unconnected-(J4-CC1-PadA5)") (class "Default")
      (node (ref "J4") (pin "A5") (pinfunction "CC1_A5") (pintype "passive"))
    )
    (net (code "88") (name "unconnected-(J4-CC2-PadB5)") (class "Default")
      (node (ref "J4") (pin "B5") (pinfunction "CC2_B5") (pintype "passive"))
    )
    (net (code "89") (name "unconnected-(J4-SUB1-PadA8)") (class "Default")
      (node (ref "J4") (pin "A8") (pinfunction "SUB1_A8") (pintype "passive"))
    )
    (net (code "90") (name "unconnected-(J4-SUB2-PadB8)") (class "Default")
      (node (ref "J4") (pin "B8") (pinfunction "SUB2_B8") (pintype "passive"))
    )
    (net (code "91") (name "unconnected-(U3-BYP-Pad4)") (class "Default")
      (node (ref "U3") (pin "4") (pinfunction "BYP_4") (pintype "passive+no_connect"))
    )
    (net (code "92") (name "unconnected-(U4-BYP-Pad4)") (class "Default")
      (node (ref "U4") (pin "4") (pinfunction "BYP_4") (pintype "passive+no_connect"))
    )
    (net (code "93") (name "unconnected-(U5-VBREF-Pad6)") (class "Default")
      (node (ref "U5") (pin "6") (pinfunction "VBREF_6") (pintype "passive+no_connect"))
    )
  )
)
